# Power_Distribution_-_Steering_Pedal_Cent.net
KiCad netlist of a schematic drawn in Altium Designer
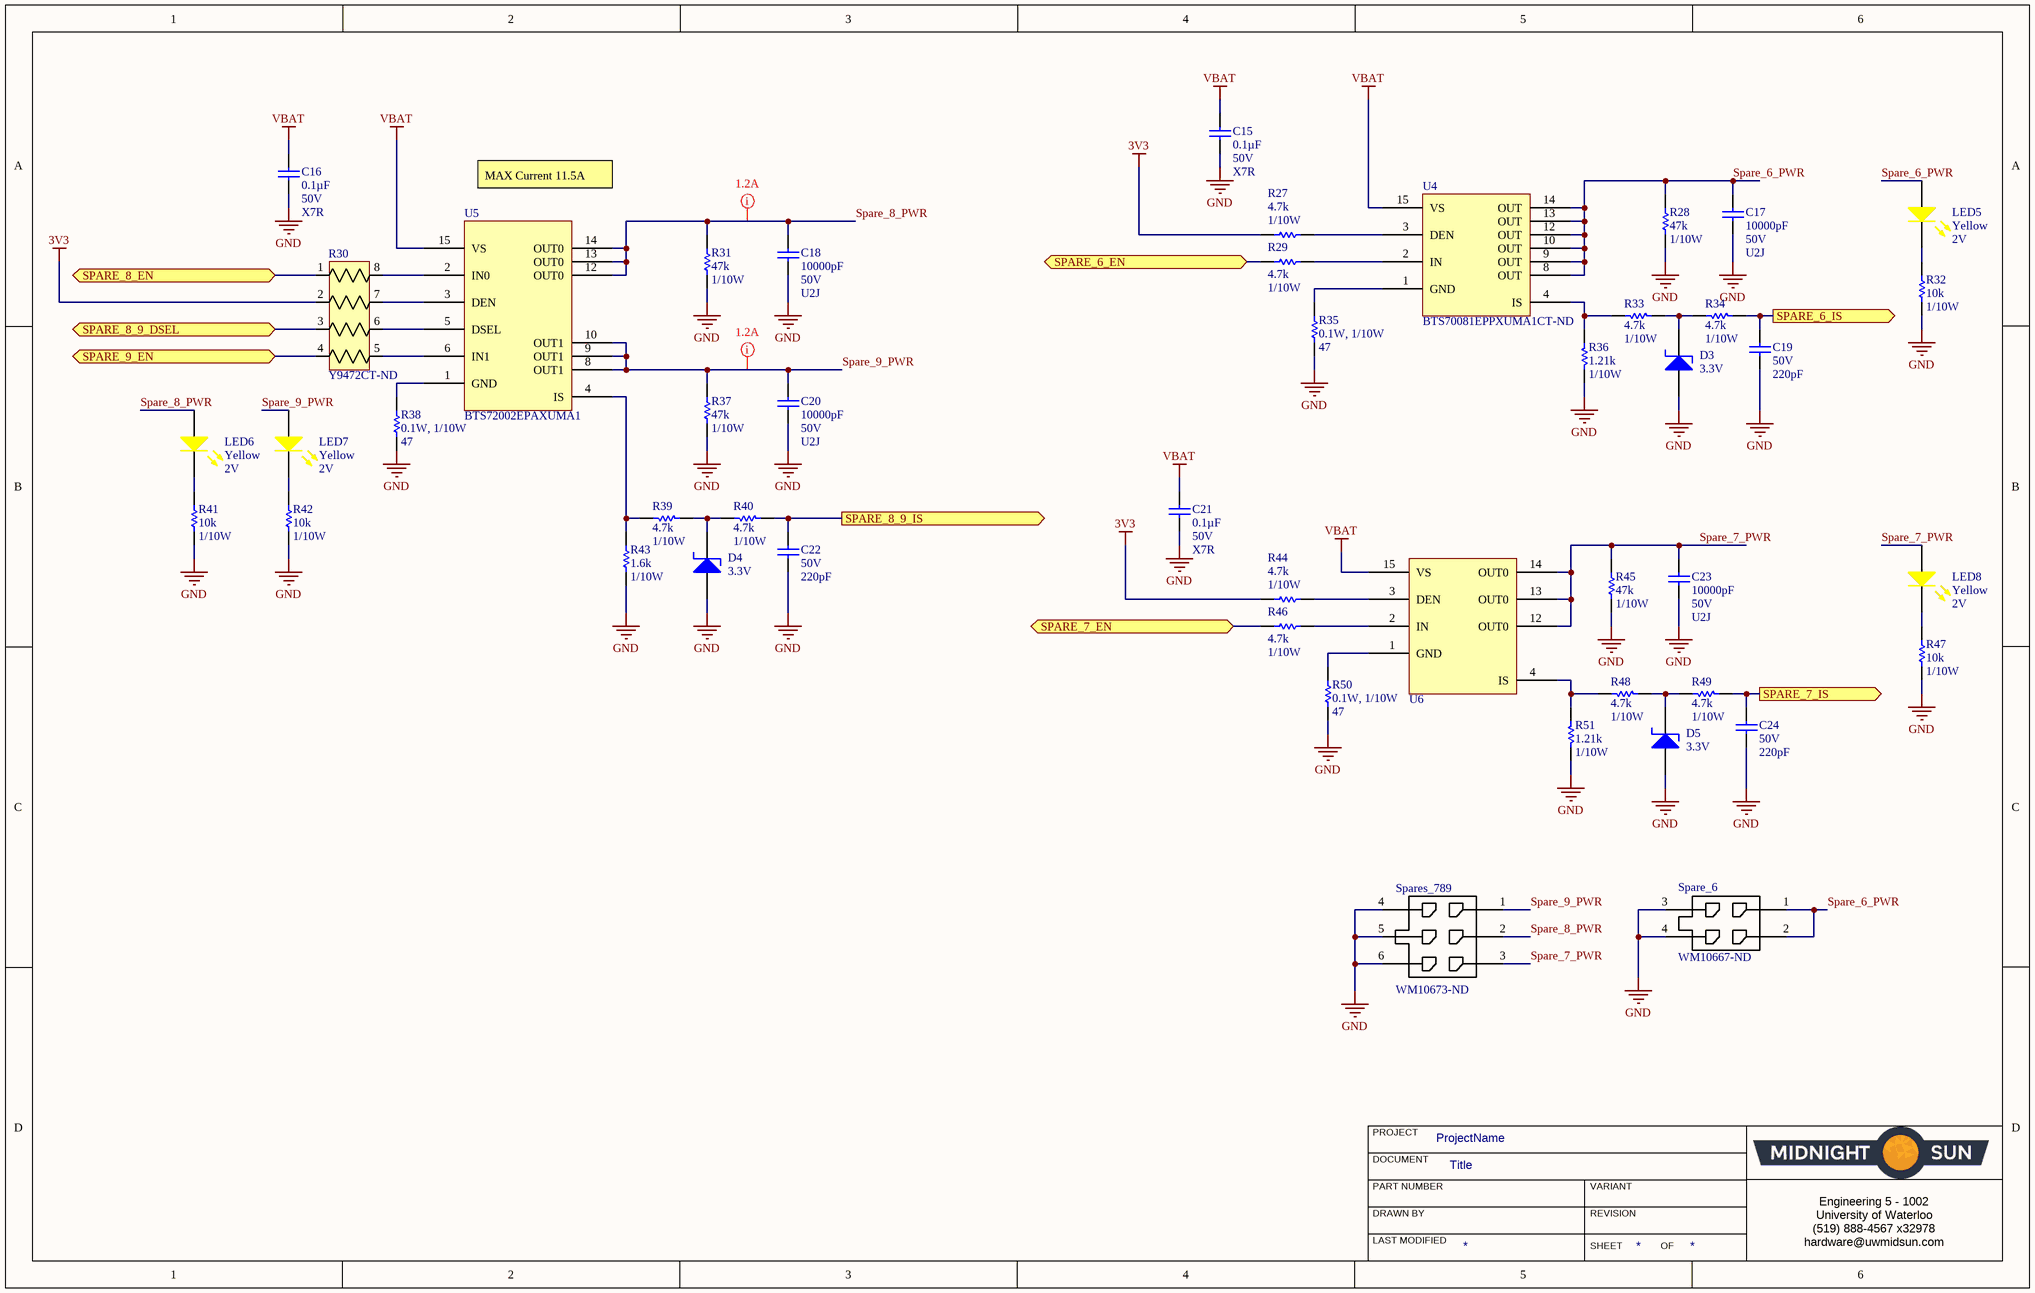
[diagram p0: Power Distribution - Steering, Pedal, Center Console, and Fan.SchDoc]

(export (version "E")
  (design (tool "Eeschema 10.0.6"))
  (components
    (comp (ref "C15")
      (value "CAP CER 0.1UF 50V 10% X7R 0603")
      (footprint "CAP, 0603")
      (description "0.10µF ±10% 50V Ceramic Capacitor X7R 0603 (1608 Metric)")
      (fields
        (field (name "TOLERANCE") "±10%")
        (field (name "CAPACITANCE") "0.1µF")
        (field (name "VOLTAGE") "50V")
        (field (name "TEMPERATURE COEFFICIENT") "X7R")
      )
      (libsource (lib "Schematic Diagrams") (part "CAP CER 0.1UF 50V 10% X7R 0603"))
    )
    (comp (ref "C16")
      (value "CAP CER 0.1UF 50V 10% X7R 0603")
      (footprint "CAP, 0603")
      (description "0.10µF ±10% 50V Ceramic Capacitor X7R 0603 (1608 Metric)")
      (fields
        (field (name "TOLERANCE") "±10%")
        (field (name "CAPACITANCE") "0.1µF")
        (field (name "VOLTAGE") "50V")
        (field (name "TEMPERATURE COEFFICIENT") "X7R")
      )
      (libsource (lib "Schematic Diagrams") (part "CAP CER 0.1UF 50V 10% X7R 0603"))
    )
    (comp (ref "C17")
      (value "CAP CER 10nF 50V 5% X7R 0603")
      (footprint "CAP, 0603")
      (description "10000pF ±5% 50V Ceramic Capacitor U2J 0603 (1608 Metric)")
      (fields
        (field (name "TOLERANCE") "±5%")
        (field (name "CAPACITANCE") "10000pF")
        (field (name "VOLTAGE") "50V")
        (field (name "TEMPERATURE COEFFICIENT") "U2J")
      )
      (libsource (lib "Schematic Diagrams") (part "CAP CER 10nF 50V 5% X7R 0603"))
    )
    (comp (ref "C18")
      (value "CAP CER 10nF 50V 5% X7R 0603")
      (footprint "CAP, 0603")
      (description "10000pF ±5% 50V Ceramic Capacitor U2J 0603 (1608 Metric)")
      (fields
        (field (name "TOLERANCE") "±5%")
        (field (name "CAPACITANCE") "10000pF")
        (field (name "VOLTAGE") "50V")
        (field (name "TEMPERATURE COEFFICIENT") "U2J")
      )
      (libsource (lib "Schematic Diagrams") (part "CAP CER 10nF 50V 5% X7R 0603"))
    )
    (comp (ref "C19")
      (value "CAP CER 220PF 50V C0G/NP0 0603")
      (footprint "CAP, 0603")
      (description "220pF ±5% 50V Ceramic Capacitor C0G, NP0 0603 (1608 Metric)")
      (fields
        (field (name "MANUFACTURER") "KEMET")
        (field (name "TOLERANCE") "5%")
        (field (name "VOLTAGE RATING") "50V")
        (field (name "CAPACITANCE") "220pF")
      )
      (libsource (lib "Schematic Diagrams") (part "CAP CER 220PF 50V C0G/NP0 0603"))
    )
    (comp (ref "C20")
      (value "CAP CER 10nF 50V 5% X7R 0603")
      (footprint "CAP, 0603")
      (description "10000pF ±5% 50V Ceramic Capacitor U2J 0603 (1608 Metric)")
      (fields
        (field (name "TOLERANCE") "±5%")
        (field (name "CAPACITANCE") "10000pF")
        (field (name "VOLTAGE") "50V")
        (field (name "TEMPERATURE COEFFICIENT") "U2J")
      )
      (libsource (lib "Schematic Diagrams") (part "CAP CER 10nF 50V 5% X7R 0603"))
    )
    (comp (ref "C21")
      (value "CAP CER 0.1UF 50V 10% X7R 0603")
      (footprint "CAP, 0603")
      (description "0.10µF ±10% 50V Ceramic Capacitor X7R 0603 (1608 Metric)")
      (fields
        (field (name "TOLERANCE") "±10%")
        (field (name "CAPACITANCE") "0.1µF")
        (field (name "VOLTAGE") "50V")
        (field (name "TEMPERATURE COEFFICIENT") "X7R")
      )
      (libsource (lib "Schematic Diagrams") (part "CAP CER 0.1UF 50V 10% X7R 0603"))
    )
    (comp (ref "C22")
      (value "CAP CER 220PF 50V C0G/NP0 0603")
      (footprint "CAP, 0603")
      (description "220pF ±5% 50V Ceramic Capacitor C0G, NP0 0603 (1608 Metric)")
      (fields
        (field (name "MANUFACTURER") "KEMET")
        (field (name "TOLERANCE") "5%")
        (field (name "VOLTAGE RATING") "50V")
        (field (name "CAPACITANCE") "220pF")
      )
      (libsource (lib "Schematic Diagrams") (part "CAP CER 220PF 50V C0G/NP0 0603"))
    )
    (comp (ref "C23")
      (value "CAP CER 10nF 50V 5% X7R 0603")
      (footprint "CAP, 0603")
      (description "10000pF ±5% 50V Ceramic Capacitor U2J 0603 (1608 Metric)")
      (fields
        (field (name "TOLERANCE") "±5%")
        (field (name "CAPACITANCE") "10000pF")
        (field (name "VOLTAGE") "50V")
        (field (name "TEMPERATURE COEFFICIENT") "U2J")
      )
      (libsource (lib "Schematic Diagrams") (part "CAP CER 10nF 50V 5% X7R 0603"))
    )
    (comp (ref "C24")
      (value "CAP CER 220PF 50V C0G/NP0 0603")
      (footprint "CAP, 0603")
      (description "220pF ±5% 50V Ceramic Capacitor C0G, NP0 0603 (1608 Metric)")
      (fields
        (field (name "MANUFACTURER") "KEMET")
        (field (name "TOLERANCE") "5%")
        (field (name "VOLTAGE RATING") "50V")
        (field (name "CAPACITANCE") "220pF")
      )
      (libsource (lib "Schematic Diagrams") (part "CAP CER 220PF 50V C0G/NP0 0603"))
    )
    (comp (ref "D3")
      (value "DIODE ZENER 3.3V 200MW SOD323")
      (footprint "sod-323")
      (description "Zener Diode 3.3V 200mW ±5% Surface Mount SOD-323")
      (fields (field (name "VOLTAGE") "3.3V"))
      (libsource (lib "Schematic Diagrams") (part "DIODE ZENER 3.3V 200MW SOD323"))
    )
    (comp (ref "D4")
      (value "DIODE ZENER 3.3V 200MW SOD323")
      (footprint "sod-323")
      (description "Zener Diode 3.3V 200mW ±5% Surface Mount SOD-323")
      (fields (field (name "VOLTAGE") "3.3V"))
      (libsource (lib "Schematic Diagrams") (part "DIODE ZENER 3.3V 200MW SOD323"))
    )
    (comp (ref "D5")
      (value "DIODE ZENER 3.3V 200MW SOD323")
      (footprint "sod-323")
      (description "Zener Diode 3.3V 200mW ±5% Surface Mount SOD-323")
      (fields (field (name "VOLTAGE") "3.3V"))
      (libsource (lib "Schematic Diagrams") (part "DIODE ZENER 3.3V 200MW SOD323"))
    )
    (comp (ref "LED5")
      (value "LED YELLOW CLEAR 2.1V 0603")
      (footprint "LED_0603")
      (description "Yellow 590nm LED Indication - Discrete 2V 0603 (1608 Metric)")
      (fields
        (field (name "MANUFACTURER") "Wurth Electronics Inc.")
        (field (name "MANUFACTURER PART NUMBER") "150060YS75000")
        (field (name "COLOR") "Yellow")
        (field (name "VOLTAGE - FORWARD (VF) (TYP)") "2V")
      )
      (libsource (lib "Schematic Diagrams") (part "LED YELLOW CLEAR 2.1V 0603"))
    )
    (comp (ref "LED6")
      (value "LED YELLOW CLEAR 2.1V 0603")
      (footprint "LED_0603")
      (description "Yellow 590nm LED Indication - Discrete 2V 0603 (1608 Metric)")
      (fields
        (field (name "MANUFACTURER") "Wurth Electronics Inc.")
        (field (name "MANUFACTURER PART NUMBER") "150060YS75000")
        (field (name "COLOR") "Yellow")
        (field (name "VOLTAGE - FORWARD (VF) (TYP)") "2V")
      )
      (libsource (lib "Schematic Diagrams") (part "LED YELLOW CLEAR 2.1V 0603"))
    )
    (comp (ref "LED7")
      (value "LED YELLOW CLEAR 2.1V 0603")
      (footprint "LED_0603")
      (description "Yellow 590nm LED Indication - Discrete 2V 0603 (1608 Metric)")
      (fields
        (field (name "MANUFACTURER") "Wurth Electronics Inc.")
        (field (name "MANUFACTURER PART NUMBER") "150060YS75000")
        (field (name "COLOR") "Yellow")
        (field (name "VOLTAGE - FORWARD (VF) (TYP)") "2V")
      )
      (libsource (lib "Schematic Diagrams") (part "LED YELLOW CLEAR 2.1V 0603"))
    )
    (comp (ref "LED8")
      (value "LED YELLOW CLEAR 2.1V 0603")
      (footprint "LED_0603")
      (description "Yellow 590nm LED Indication - Discrete 2V 0603 (1608 Metric)")
      (fields
        (field (name "MANUFACTURER") "Wurth Electronics Inc.")
        (field (name "MANUFACTURER PART NUMBER") "150060YS75000")
        (field (name "COLOR") "Yellow")
        (field (name "VOLTAGE - FORWARD (VF) (TYP)") "2V")
      )
      (libsource (lib "Schematic Diagrams") (part "LED YELLOW CLEAR 2.1V 0603"))
    )
    (comp (ref "R27")
      (value "RES 4.7K OHM 1% 1/10W 0603")
      (footprint "RES, 0603")
      (description "4.7k Ohm ±1% 0.1W, 1/10W Chip Resistor 0603 (1608 Metric) Moisture Resistant Thick Film")
      (fields
        (field (name "TOLERANCE") "±1%")
        (field (name "RESISTANCE (OHMS)") "4.7k")
        (field (name "POWER (WATTS)") "1/10W")
      )
      (libsource (lib "Schematic Diagrams") (part "RES 4.7K OHM 1% 1/10W 0603"))
    )
    (comp (ref "R28")
      (value "RES 47K OHM 1% 1/10W 0603")
      (footprint "RES, 0603")
      (description "47 kOhms ±1% 0.1W, 1/10W Chip Resistor 0603 (1608 Metric) Automotive AEC-Q200 Thick Film")
      (fields
        (field (name "MANUFACTURER") "Panasonic")
        (field (name "MANUFACTURER PART NUMBER") "ERJ3EKF4702V")
        (field (name "RESISTANCE") "47k")
        (field (name "POWER RATING") "1/10W")
      )
      (libsource (lib "Schematic Diagrams") (part "RES 47K OHM 1% 1/10W 0603"))
    )
    (comp (ref "R29")
      (value "RES 4.7K OHM 1% 1/10W 0603")
      (footprint "RES, 0603")
      (description "4.7k Ohm ±1% 0.1W, 1/10W Chip Resistor 0603 (1608 Metric) Moisture Resistant Thick Film")
      (fields
        (field (name "TOLERANCE") "±1%")
        (field (name "RESISTANCE (OHMS)") "4.7k")
        (field (name "POWER (WATTS)") "1/10W")
      )
      (libsource (lib "Schematic Diagrams") (part "RES 4.7K OHM 1% 1/10W 0603"))
    )
    (comp (ref "R30")
      (value "RES ARRAY 4 RES 4.7K OHM 1206")
      (footprint "RES ARRAY 4RES 1206")
      (fields (field (name "TOLERANCE") "±5%") (field (name "SUPPLIER PART NUMBER 1") "Y9472CT-ND"))
      (libsource (lib "Schematic Diagrams") (part "RES ARRAY 4 RES 4.7K OHM 1206"))
    )
    (comp (ref "R31")
      (value "RES 47K OHM 1% 1/10W 0603")
      (footprint "RES, 0603")
      (description "47 kOhms ±1% 0.1W, 1/10W Chip Resistor 0603 (1608 Metric) Automotive AEC-Q200 Thick Film")
      (fields
        (field (name "MANUFACTURER") "Panasonic")
        (field (name "MANUFACTURER PART NUMBER") "ERJ3EKF4702V")
        (field (name "RESISTANCE") "47k")
        (field (name "POWER RATING") "1/10W")
      )
      (libsource (lib "Schematic Diagrams") (part "RES 47K OHM 1% 1/10W 0603"))
    )
    (comp (ref "R32")
      (value "RES 10K OHM 1% 1/10W 0603")
      (footprint "RES, 0603")
      (description "RES SMD 10K OHM 1% 1/10W 0603")
      (fields
        (field (name "TOLERANCE") "±1%")
        (field (name "RESISTANCE") "10k")
        (field (name "POWER") "1/10W")
      )
      (libsource (lib "Schematic Diagrams") (part "RES 10K OHM 1% 1/10W 0603"))
    )
    (comp (ref "R33")
      (value "RES 4.7K OHM 1% 1/10W 0603")
      (footprint "RES, 0603")
      (description "4.7k Ohm ±1% 0.1W, 1/10W Chip Resistor 0603 (1608 Metric) Moisture Resistant Thick Film")
      (fields
        (field (name "TOLERANCE") "±1%")
        (field (name "RESISTANCE (OHMS)") "4.7k")
        (field (name "POWER (WATTS)") "1/10W")
      )
      (libsource (lib "Schematic Diagrams") (part "RES 4.7K OHM 1% 1/10W 0603"))
    )
    (comp (ref "R34")
      (value "RES 4.7K OHM 1% 1/10W 0603")
      (footprint "RES, 0603")
      (description "4.7k Ohm ±1% 0.1W, 1/10W Chip Resistor 0603 (1608 Metric) Moisture Resistant Thick Film")
      (fields
        (field (name "TOLERANCE") "±1%")
        (field (name "RESISTANCE (OHMS)") "4.7k")
        (field (name "POWER (WATTS)") "1/10W")
      )
      (libsource (lib "Schematic Diagrams") (part "RES 4.7K OHM 1% 1/10W 0603"))
    )
    (comp (ref "R35")
      (value "RES SMD 47 OHM 1% 1/10W 0603")
      (footprint "RES, 0603")
      (fields
        (field (name "TOLERANCE") "±1%")
        (field (name "POWER (WATTS)") "0.1W, 1/10W")
        (field (name "VALUES") "47")
      )
      (libsource (lib "Schematic Diagrams") (part "RES SMD 47 OHM 1% 1/10W 0603"))
    )
    (comp (ref "R36")
      (value "RES 1.21K OHM 1% 1/10W 0603")
      (footprint "RES, 0603")
      (description "1.21k Ohm ±1% 0.1W, 1/10W Chip Resistor 0603 (1608 Metric) Moisture Resistant Thick Film")
      (fields
        (field (name "TOLERANCE") "±1%")
        (field (name "RESISTANCE") "1.21k")
        (field (name "POWER") "1/10W")
      )
      (libsource (lib "Schematic Diagrams") (part "RES 1.21K OHM 1% 1/10W 0603"))
    )
    (comp (ref "R37")
      (value "RES 47K OHM 1% 1/10W 0603")
      (footprint "RES, 0603")
      (description "47 kOhms ±1% 0.1W, 1/10W Chip Resistor 0603 (1608 Metric) Automotive AEC-Q200 Thick Film")
      (fields
        (field (name "MANUFACTURER") "Panasonic")
        (field (name "MANUFACTURER PART NUMBER") "ERJ3EKF4702V")
        (field (name "RESISTANCE") "47k")
        (field (name "POWER RATING") "1/10W")
      )
      (libsource (lib "Schematic Diagrams") (part "RES 47K OHM 1% 1/10W 0603"))
    )
    (comp (ref "R38")
      (value "RES SMD 47 OHM 1% 1/10W 0603")
      (footprint "RES, 0603")
      (fields
        (field (name "TOLERANCE") "±1%")
        (field (name "POWER (WATTS)") "0.1W, 1/10W")
        (field (name "VALUES") "47")
      )
      (libsource (lib "Schematic Diagrams") (part "RES SMD 47 OHM 1% 1/10W 0603"))
    )
    (comp (ref "R39")
      (value "RES 4.7K OHM 1% 1/10W 0603")
      (footprint "RES, 0603")
      (description "4.7k Ohm ±1% 0.1W, 1/10W Chip Resistor 0603 (1608 Metric) Moisture Resistant Thick Film")
      (fields
        (field (name "TOLERANCE") "±1%")
        (field (name "RESISTANCE (OHMS)") "4.7k")
        (field (name "POWER (WATTS)") "1/10W")
      )
      (libsource (lib "Schematic Diagrams") (part "RES 4.7K OHM 1% 1/10W 0603"))
    )
    (comp (ref "R40")
      (value "RES 4.7K OHM 1% 1/10W 0603")
      (footprint "RES, 0603")
      (description "4.7k Ohm ±1% 0.1W, 1/10W Chip Resistor 0603 (1608 Metric) Moisture Resistant Thick Film")
      (fields
        (field (name "TOLERANCE") "±1%")
        (field (name "RESISTANCE (OHMS)") "4.7k")
        (field (name "POWER (WATTS)") "1/10W")
      )
      (libsource (lib "Schematic Diagrams") (part "RES 4.7K OHM 1% 1/10W 0603"))
    )
    (comp (ref "R41")
      (value "RES 10K OHM 1% 1/10W 0603")
      (footprint "RES, 0603")
      (description "RES SMD 10K OHM 1% 1/10W 0603")
      (fields
        (field (name "TOLERANCE") "±1%")
        (field (name "RESISTANCE") "10k")
        (field (name "POWER") "1/10W")
      )
      (libsource (lib "Schematic Diagrams") (part "RES 10K OHM 1% 1/10W 0603"))
    )
    (comp (ref "R42")
      (value "RES 10K OHM 1% 1/10W 0603")
      (footprint "RES, 0603")
      (description "RES SMD 10K OHM 1% 1/10W 0603")
      (fields
        (field (name "TOLERANCE") "±1%")
        (field (name "RESISTANCE") "10k")
        (field (name "POWER") "1/10W")
      )
      (libsource (lib "Schematic Diagrams") (part "RES 10K OHM 1% 1/10W 0603"))
    )
    (comp (ref "R43")
      (value "RES 1.6K OHM 1% 1/10W 0603")
      (footprint "RES, 0603")
      (description "1.6 kOhms ±1% 0.1W, 1/10W Chip Resistor 0603 (1608 Metric) Moisture Resistant Thick Film")
      (fields
        (field (name "MANUFACTURER") "Yageo")
        (field (name "MANUFACTURER PART NUMBER") "RC0603FR-071K6L")
        (field (name "RESISTANCE") "1.6k")
        (field (name "POWER RATING") "1/10W")
      )
      (libsource (lib "Schematic Diagrams") (part "RES 1.6K OHM 1% 1/10W 0603"))
    )
    (comp (ref "R44")
      (value "RES 4.7K OHM 1% 1/10W 0603")
      (footprint "RES, 0603")
      (description "4.7k Ohm ±1% 0.1W, 1/10W Chip Resistor 0603 (1608 Metric) Moisture Resistant Thick Film")
      (fields
        (field (name "TOLERANCE") "±1%")
        (field (name "RESISTANCE (OHMS)") "4.7k")
        (field (name "POWER (WATTS)") "1/10W")
      )
      (libsource (lib "Schematic Diagrams") (part "RES 4.7K OHM 1% 1/10W 0603"))
    )
    (comp (ref "R45")
      (value "RES 47K OHM 1% 1/10W 0603")
      (footprint "RES, 0603")
      (description "47 kOhms ±1% 0.1W, 1/10W Chip Resistor 0603 (1608 Metric) Automotive AEC-Q200 Thick Film")
      (fields
        (field (name "MANUFACTURER") "Panasonic")
        (field (name "MANUFACTURER PART NUMBER") "ERJ3EKF4702V")
        (field (name "RESISTANCE") "47k")
        (field (name "POWER RATING") "1/10W")
      )
      (libsource (lib "Schematic Diagrams") (part "RES 47K OHM 1% 1/10W 0603"))
    )
    (comp (ref "R46")
      (value "RES 4.7K OHM 1% 1/10W 0603")
      (footprint "RES, 0603")
      (description "4.7k Ohm ±1% 0.1W, 1/10W Chip Resistor 0603 (1608 Metric) Moisture Resistant Thick Film")
      (fields
        (field (name "TOLERANCE") "±1%")
        (field (name "RESISTANCE (OHMS)") "4.7k")
        (field (name "POWER (WATTS)") "1/10W")
      )
      (libsource (lib "Schematic Diagrams") (part "RES 4.7K OHM 1% 1/10W 0603"))
    )
    (comp (ref "R47")
      (value "RES 10K OHM 1% 1/10W 0603")
      (footprint "RES, 0603")
      (description "RES SMD 10K OHM 1% 1/10W 0603")
      (fields
        (field (name "TOLERANCE") "±1%")
        (field (name "RESISTANCE") "10k")
        (field (name "POWER") "1/10W")
      )
      (libsource (lib "Schematic Diagrams") (part "RES 10K OHM 1% 1/10W 0603"))
    )
    (comp (ref "R48")
      (value "RES 4.7K OHM 1% 1/10W 0603")
      (footprint "RES, 0603")
      (description "4.7k Ohm ±1% 0.1W, 1/10W Chip Resistor 0603 (1608 Metric) Moisture Resistant Thick Film")
      (fields
        (field (name "TOLERANCE") "±1%")
        (field (name "RESISTANCE (OHMS)") "4.7k")
        (field (name "POWER (WATTS)") "1/10W")
      )
      (libsource (lib "Schematic Diagrams") (part "RES 4.7K OHM 1% 1/10W 0603"))
    )
    (comp (ref "R49")
      (value "RES 4.7K OHM 1% 1/10W 0603")
      (footprint "RES, 0603")
      (description "4.7k Ohm ±1% 0.1W, 1/10W Chip Resistor 0603 (1608 Metric) Moisture Resistant Thick Film")
      (fields
        (field (name "TOLERANCE") "±1%")
        (field (name "RESISTANCE (OHMS)") "4.7k")
        (field (name "POWER (WATTS)") "1/10W")
      )
      (libsource (lib "Schematic Diagrams") (part "RES 4.7K OHM 1% 1/10W 0603"))
    )
    (comp (ref "R50")
      (value "RES SMD 47 OHM 1% 1/10W 0603")
      (footprint "RES, 0603")
      (fields
        (field (name "TOLERANCE") "±1%")
        (field (name "POWER (WATTS)") "0.1W, 1/10W")
        (field (name "VALUES") "47")
      )
      (libsource (lib "Schematic Diagrams") (part "RES SMD 47 OHM 1% 1/10W 0603"))
    )
    (comp (ref "R51")
      (value "RES 1.21K OHM 1% 1/10W 0603")
      (footprint "RES, 0603")
      (description "1.21k Ohm ±1% 0.1W, 1/10W Chip Resistor 0603 (1608 Metric) Moisture Resistant Thick Film")
      (fields
        (field (name "TOLERANCE") "±1%")
        (field (name "RESISTANCE") "1.21k")
        (field (name "POWER") "1/10W")
      )
      (libsource (lib "Schematic Diagrams") (part "RES 1.21K OHM 1% 1/10W 0603"))
    )
    (comp (ref "Spares_789")
      (value "CONN 6POS MICRO-FIT 3mm")
      (footprint "CONN, 6POS MICRO-FIT 3MM")
      (description "Connector Header Through Hole 6 position 0.118\" (3.00mm)")
      (fields (field (name "SUPPLIER PART NUMBER 1") "WM10673-ND"))
      (libsource (lib "Schematic Diagrams") (part "CONN 6POS MICRO-FIT 3mm"))
    )
    (comp (ref "Spare_6")
      (value "CONN 4POS MICRO-FIT 3mm")
      (footprint "CONN 4POS MICROFIT (2x2)")
      (fields
        (field (name "MANUFACTURER") "Molex, LLC")
        (field (name "MANUFACTURER PART NUMBER") "430450427")
        (field (name "SUPPLIER PART NUMBER 1") "WM10667-ND")
      )
      (libsource (lib "Schematic Diagrams") (part "CONN 4POS MICRO-FIT 3mm"))
    )
    (comp (ref "U4")
      (value "IC LOAD SWITCH BTS70081EPPXUMA1")
      (footprint "IC LOAD SWITCH PG-TSDSO-14-22")
      (description "Power Switch/Driver 1:1 N-Channel 11A PG-TSDSO-14-22")
      (fields
        (field (name "MANUFACTURER") "Infineon")
        (field (name "MANUFACTURER PART NUMBER") "BTS70081EPPXUMA1CT-ND")
      )
      (libsource (lib "Schematic Diagrams") (part "IC LOAD SWITCH BTS70081EPPXUMA1"))
    )
    (comp (ref "U5")
      (value "IC LOAD SWITCH BTS7200-2EPA PG-TSDSO-14_1")
      (footprint "IC LOAD SWITCH PG-TSDSO-14-22")
      (description "Power Switch/Driver 1:1 N-Channel 1.2A PG-TSDSO-14-22")
      (fields
        (field (name "MANUFACTURER") "Infineon")
        (field (name "MANUFACTURER PART NUMBER") "BTS72002EPAXUMA1")
      )
      (libsource (lib "Schematic Diagrams") (part "IC LOAD SWITCH BTS7200-2EPA PG-TSDSO-14_1"))
    )
    (comp (ref "U6")
      (value "IC LOAD SWITCH BTS70401EPA PG-TSDSO-14-22")
      (footprint "IC LOAD SWITCH PG-TSDSO-14-22")
      (description "Power Switch/Driver 1:1 N-Channel 4.5A PG-TSDSO-14-22")
      (fields
        (field (name "MANUFACTURER") "Infineon")
        (field (name "MANUFACTURER PART NUMBER") "BTS70401EPAXUMA1")
      )
      (libsource (lib "Schematic Diagrams") (part "IC LOAD SWITCH BTS70401EPA PG-TSDSO-14-22"))
    )
  )
  (nets
    (net (code "1") (name "/SPARE_6_EN") (class "Default")
      (node (ref "R29") (pin "1") (pinfunction "1_1") (pintype "passive"))
    )
    (net (code "2") (name "/SPARE_6_IS") (class "Default")
      (node (ref "C19") (pin "1") (pinfunction "1_1") (pintype "passive"))
      (node (ref "R34") (pin "1") (pinfunction "1_1") (pintype "passive"))
    )
    (net (code "3") (name "/SPARE_7_EN") (class "Default")
      (node (ref "R46") (pin "1") (pinfunction "1_1") (pintype "passive"))
    )
    (net (code "4") (name "/SPARE_7_IS") (class "Default")
      (node (ref "C24") (pin "1") (pinfunction "1_1") (pintype "passive"))
      (node (ref "R49") (pin "1") (pinfunction "1_1") (pintype "passive"))
    )
    (net (code "5") (name "/SPARE_8_9_DSEL") (class "Default")
      (node (ref "R30") (pin "3") (pinfunction "3_3") (pintype "passive"))
    )
    (net (code "6") (name "/SPARE_8_9_IS") (class "Default")
      (node (ref "C22") (pin "1") (pinfunction "1_1") (pintype "passive"))
      (node (ref "R40") (pin "1") (pinfunction "1_1") (pintype "passive"))
    )
    (net (code "7") (name "/SPARE_8_EN") (class "Default")
      (node (ref "R30") (pin "1") (pinfunction "1_1") (pintype "passive"))
    )
    (net (code "8") (name "/SPARE_9_EN") (class "Default")
      (node (ref "R30") (pin "4") (pinfunction "4_4") (pintype "passive"))
    )
    (net (code "9") (name "/Spare_6_PWR") (class "Default")
      (node (ref "C17") (pin "1") (pinfunction "1_1") (pintype "passive"))
      (node (ref "LED5") (pin "1") (pinfunction "A_1") (pintype "passive"))
      (node (ref "R28") (pin "1") (pinfunction "1_1") (pintype "passive"))
      (node (ref "Spare_6") (pin "1") (pinfunction "1_1") (pintype "passive"))
      (node (ref "Spare_6") (pin "2") (pinfunction "2_2") (pintype "passive"))
      (node (ref "U4") (pin "10") (pinfunction "OUT_10") (pintype "passive"))
      (node (ref "U4") (pin "12") (pinfunction "OUT_12") (pintype "passive"))
      (node (ref "U4") (pin "13") (pinfunction "OUT_13") (pintype "passive"))
      (node (ref "U4") (pin "14") (pinfunction "OUT_14") (pintype "passive"))
      (node (ref "U4") (pin "8") (pinfunction "OUT_8") (pintype "passive"))
      (node (ref "U4") (pin "9") (pinfunction "OUT_9") (pintype "passive"))
    )
    (net (code "10") (name "/Spare_7_PWR") (class "Default")
      (node (ref "C23") (pin "1") (pinfunction "1_1") (pintype "passive"))
      (node (ref "LED8") (pin "1") (pinfunction "A_1") (pintype "passive"))
      (node (ref "R45") (pin "1") (pinfunction "1_1") (pintype "passive"))
      (node (ref "Spares_789") (pin "3") (pinfunction "3_3") (pintype "passive"))
      (node (ref "U6") (pin "12") (pinfunction "OUT0_12") (pintype "passive"))
      (node (ref "U6") (pin "13") (pinfunction "OUT0_13") (pintype "passive"))
      (node (ref "U6") (pin "14") (pinfunction "OUT0_14") (pintype "passive"))
    )
    (net (code "11") (name "/Spare_8_PWR") (class "Default")
      (node (ref "C18") (pin "1") (pinfunction "1_1") (pintype "passive"))
      (node (ref "LED6") (pin "1") (pinfunction "A_1") (pintype "passive"))
      (node (ref "R31") (pin "1") (pinfunction "1_1") (pintype "passive"))
      (node (ref "Spares_789") (pin "2") (pinfunction "2_2") (pintype "passive"))
      (node (ref "U5") (pin "12") (pinfunction "OUT0_12") (pintype "passive"))
      (node (ref "U5") (pin "13") (pinfunction "OUT0_13") (pintype "passive"))
      (node (ref "U5") (pin "14") (pinfunction "OUT0_14") (pintype "passive"))
    )
    (net (code "12") (name "/Spare_9_PWR") (class "Default")
      (node (ref "C20") (pin "1") (pinfunction "1_1") (pintype "passive"))
      (node (ref "LED7") (pin "1") (pinfunction "A_1") (pintype "passive"))
      (node (ref "R37") (pin "1") (pinfunction "1_1") (pintype "passive"))
      (node (ref "Spares_789") (pin "1") (pinfunction "1_1") (pintype "passive"))
      (node (ref "U5") (pin "10") (pinfunction "OUT1_10") (pintype "passive"))
      (node (ref "U5") (pin "8") (pinfunction "OUT1_8") (pintype "passive"))
      (node (ref "U5") (pin "9") (pinfunction "OUT1_9") (pintype "passive"))
    )
    (net (code "13") (name "3V3") (class "Default")
      (node (ref "R27") (pin "1") (pinfunction "1_1") (pintype "passive"))
      (node (ref "R30") (pin "2") (pinfunction "2_2") (pintype "passive"))
      (node (ref "R44") (pin "1") (pinfunction "1_1") (pintype "passive"))
    )
    (net (code "14") (name "GND") (class "Default")
      (node (ref "C15") (pin "2") (pinfunction "2_2") (pintype "passive"))
      (node (ref "C16") (pin "2") (pinfunction "2_2") (pintype "passive"))
      (node (ref "C17") (pin "2") (pinfunction "2_2") (pintype "passive"))
      (node (ref "C18") (pin "2") (pinfunction "2_2") (pintype "passive"))
      (node (ref "C19") (pin "2") (pinfunction "2_2") (pintype "passive"))
      (node (ref "C20") (pin "2") (pinfunction "2_2") (pintype "passive"))
      (node (ref "C21") (pin "2") (pinfunction "2_2") (pintype "passive"))
      (node (ref "C22") (pin "2") (pinfunction "2_2") (pintype "passive"))
      (node (ref "C23") (pin "2") (pinfunction "2_2") (pintype "passive"))
      (node (ref "C24") (pin "2") (pinfunction "2_2") (pintype "passive"))
      (node (ref "D3") (pin "1") (pinfunction "A_1") (pintype "passive"))
      (node (ref "D4") (pin "1") (pinfunction "A_1") (pintype "passive"))
      (node (ref "D5") (pin "1") (pinfunction "A_1") (pintype "passive"))
      (node (ref "R28") (pin "2") (pinfunction "2_2") (pintype "passive"))
      (node (ref "R31") (pin "2") (pinfunction "2_2") (pintype "passive"))
      (node (ref "R32") (pin "2") (pinfunction "2_2") (pintype "passive"))
      (node (ref "R35") (pin "2") (pinfunction "2_2") (pintype "passive"))
      (node (ref "R36") (pin "2") (pinfunction "2_2") (pintype "passive"))
      (node (ref "R37") (pin "2") (pinfunction "2_2") (pintype "passive"))
      (node (ref "R38") (pin "2") (pinfunction "2_2") (pintype "passive"))
      (node (ref "R41") (pin "2") (pinfunction "2_2") (pintype "passive"))
      (node (ref "R42") (pin "2") (pinfunction "2_2") (pintype "passive"))
      (node (ref "R43") (pin "2") (pinfunction "2_2") (pintype "passive"))
      (node (ref "R45") (pin "2") (pinfunction "2_2") (pintype "passive"))
      (node (ref "R47") (pin "2") (pinfunction "2_2") (pintype "passive"))
      (node (ref "R50") (pin "2") (pinfunction "2_2") (pintype "passive"))
      (node (ref "R51") (pin "2") (pinfunction "2_2") (pintype "passive"))
      (node (ref "Spare_6") (pin "3") (pinfunction "3_3") (pintype "passive"))
      (node (ref "Spare_6") (pin "4") (pinfunction "4_4") (pintype "passive"))
      (node (ref "Spares_789") (pin "4") (pinfunction "4_4") (pintype "passive"))
      (node (ref "Spares_789") (pin "5") (pinfunction "5_5") (pintype "passive"))
      (node (ref "Spares_789") (pin "6") (pinfunction "6_6") (pintype "passive"))
    )
    (net (code "15") (name "Net-(D3-K)") (class "Default")
      (node (ref "D3") (pin "2") (pinfunction "K_2") (pintype "passive"))
      (node (ref "R33") (pin "1") (pinfunction "1_1") (pintype "passive"))
      (node (ref "R34") (pin "2") (pinfunction "2_2") (pintype "passive"))
    )
    (net (code "16") (name "Net-(D4-K)") (class "Default")
      (node (ref "D4") (pin "2") (pinfunction "K_2") (pintype "passive"))
      (node (ref "R39") (pin "1") (pinfunction "1_1") (pintype "passive"))
      (node (ref "R40") (pin "2") (pinfunction "2_2") (pintype "passive"))
    )
    (net (code "17") (name "Net-(D5-K)") (class "Default")
      (node (ref "D5") (pin "2") (pinfunction "K_2") (pintype "passive"))
      (node (ref "R48") (pin "1") (pinfunction "1_1") (pintype "passive"))
      (node (ref "R49") (pin "2") (pinfunction "2_2") (pintype "passive"))
    )
    (net (code "18") (name "Net-(LED5-K)") (class "Default")
      (node (ref "LED5") (pin "2") (pinfunction "K_2") (pintype "passive"))
      (node (ref "R32") (pin "1") (pinfunction "1_1") (pintype "passive"))
    )
    (net (code "19") (name "Net-(LED6-K)") (class "Default")
      (node (ref "LED6") (pin "2") (pinfunction "K_2") (pintype "passive"))
      (node (ref "R41") (pin "1") (pinfunction "1_1") (pintype "passive"))
    )
    (net (code "20") (name "Net-(LED7-K)") (class "Default")
      (node (ref "LED7") (pin "2") (pinfunction "K_2") (pintype "passive"))
      (node (ref "R42") (pin "1") (pinfunction "1_1") (pintype "passive"))
    )
    (net (code "21") (name "Net-(LED8-K)") (class "Default")
      (node (ref "LED8") (pin "2") (pinfunction "K_2") (pintype "passive"))
      (node (ref "R47") (pin "1") (pinfunction "1_1") (pintype "passive"))
    )
    (net (code "22") (name "Net-(U4-DEN)") (class "Default")
      (node (ref "R27") (pin "2") (pinfunction "2_2") (pintype "passive"))
      (node (ref "U4") (pin "3") (pinfunction "DEN_3") (pintype "passive"))
    )
    (net (code "23") (name "Net-(U4-GND)") (class "Default")
      (node (ref "R35") (pin "1") (pinfunction "1_1") (pintype "passive"))
      (node (ref "U4") (pin "1") (pinfunction "GND_1") (pintype "passive"))
    )
    (net (code "24") (name "Net-(U4-IN)") (class "Default")
      (node (ref "R29") (pin "2") (pinfunction "2_2") (pintype "passive"))
      (node (ref "U4") (pin "2") (pinfunction "IN_2") (pintype "passive"))
    )
    (net (code "25") (name "Net-(U4-IS)") (class "Default")
      (node (ref "R33") (pin "2") (pinfunction "2_2") (pintype "passive"))
      (node (ref "R36") (pin "1") (pinfunction "1_1") (pintype "passive"))
      (node (ref "U4") (pin "4") (pinfunction "IS_4") (pintype "passive"))
    )
    (net (code "26") (name "Net-(U5-DEN)") (class "Default")
      (node (ref "R30") (pin "7") (pinfunction "7_7") (pintype "passive"))
      (node (ref "U5") (pin "3") (pinfunction "DEN_3") (pintype "passive"))
    )
    (net (code "27") (name "Net-(U5-DSEL)") (class "Default")
      (node (ref "R30") (pin "6") (pinfunction "6_6") (pintype "passive"))
      (node (ref "U5") (pin "5") (pinfunction "DSEL_5") (pintype "passive"))
    )
    (net (code "28") (name "Net-(U5-GND)") (class "Default")
      (node (ref "R38") (pin "1") (pinfunction "1_1") (pintype "passive"))
      (node (ref "U5") (pin "1") (pinfunction "GND_1") (pintype "passive"))
    )
    (net (code "29") (name "Net-(U5-IN0)") (class "Default")
      (node (ref "R30") (pin "8") (pinfunction "8_8") (pintype "passive"))
      (node (ref "U5") (pin "2") (pinfunction "IN0_2") (pintype "passive"))
    )
    (net (code "30") (name "Net-(U5-IN1)") (class "Default")
      (node (ref "R30") (pin "5") (pinfunction "5_5") (pintype "passive"))
      (node (ref "U5") (pin "6") (pinfunction "IN1_6") (pintype "passive"))
    )
    (net (code "31") (name "Net-(U5-IS)") (class "Default")
      (node (ref "R39") (pin "2") (pinfunction "2_2") (pintype "passive"))
      (node (ref "R43") (pin "1") (pinfunction "1_1") (pintype "passive"))
      (node (ref "U5") (pin "4") (pinfunction "IS_4") (pintype "passive"))
    )
    (net (code "32") (name "Net-(U6-DEN)") (class "Default")
      (node (ref "R44") (pin "2") (pinfunction "2_2") (pintype "passive"))
      (node (ref "U6") (pin "3") (pinfunction "DEN_3") (pintype "passive"))
    )
    (net (code "33") (name "Net-(U6-GND)") (class "Default")
      (node (ref "R50") (pin "1") (pinfunction "1_1") (pintype "passive"))
      (node (ref "U6") (pin "1") (pinfunction "GND_1") (pintype "passive"))
    )
    (net (code "34") (name "Net-(U6-IN)") (class "Default")
      (node (ref "R46") (pin "2") (pinfunction "2_2") (pintype "passive"))
      (node (ref "U6") (pin "2") (pinfunction "IN_2") (pintype "passive"))
    )
    (net (code "35") (name "Net-(U6-IS)") (class "Default")
      (node (ref "R48") (pin "2") (pinfunction "2_2") (pintype "passive"))
      (node (ref "R51") (pin "1") (pinfunction "1_1") (pintype "passive"))
      (node (ref "U6") (pin "4") (pinfunction "IS_4") (pintype "passive"))
    )
    (net (code "36") (name "VBAT") (class "Default")
      (node (ref "C15") (pin "1") (pinfunction "1_1") (pintype "passive"))
      (node (ref "C16") (pin "1") (pinfunction "1_1") (pintype "passive"))
      (node (ref "C21") (pin "1") (pinfunction "1_1") (pintype "passive"))
      (node (ref "U4") (pin "15") (pinfunction "VS_15") (pintype "passive"))
      (node (ref "U5") (pin "15") (pinfunction "VS_15") (pintype "passive"))
      (node (ref "U6") (pin "15") (pinfunction "VS_15") (pintype "passive"))
    )
  )
)
